# TOP.net
KiCad netlist of a schematic drawn in Altium Designer
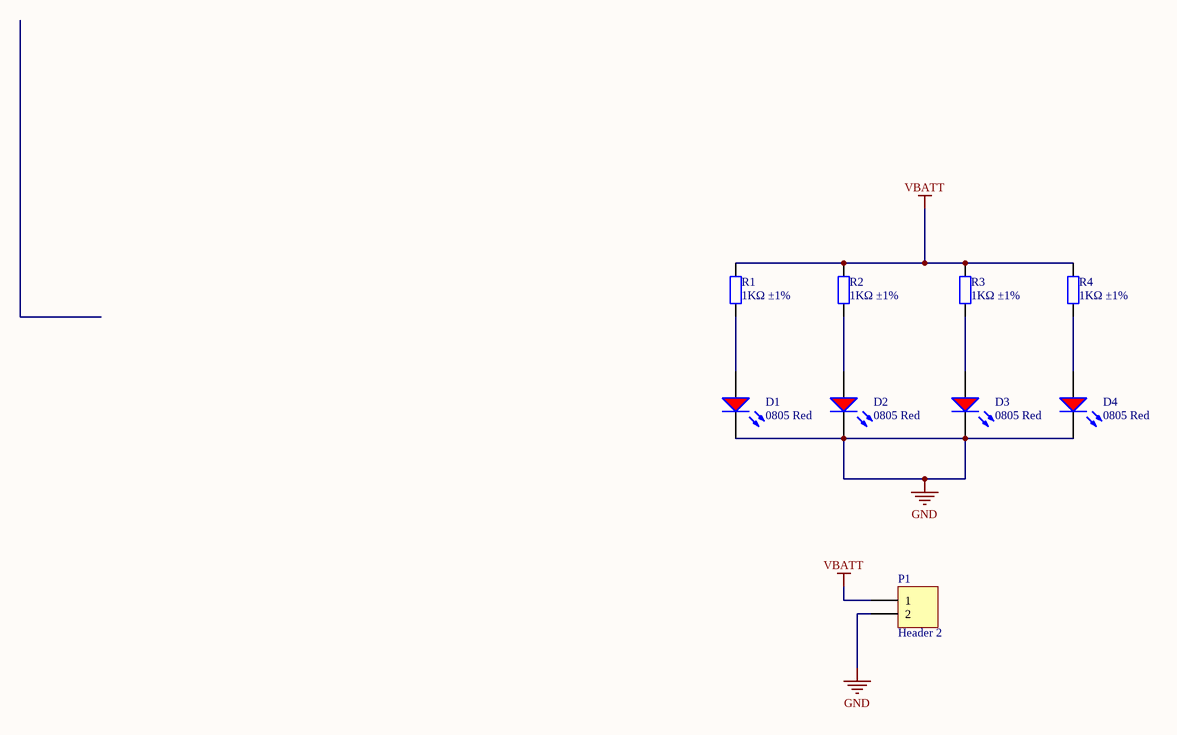
[diagram p0: TOP.SchDoc]

(export (version "E")
  (design (tool "Eeschema 10.0.6"))
  (components
    (comp (ref "D1")
      (value "0805 Red")
      (footprint "0805_LED_S1")
      (description "LED")
      (libsource (lib "Miscellaneous Devices LC") (part "0805 LED Red"))
    )
    (comp (ref "D2")
      (value "0805 Red")
      (footprint "0805_LED_S1")
      (description "LED")
      (libsource (lib "Miscellaneous Devices LC") (part "0805 LED Red"))
    )
    (comp (ref "D3")
      (value "0805 Red")
      (footprint "0805_LED_S1")
      (description "LED")
      (libsource (lib "Miscellaneous Devices LC") (part "0805 LED Red"))
    )
    (comp (ref "D4")
      (value "0805 Red")
      (footprint "0805_LED_S1")
      (description "LED")
      (libsource (lib "Miscellaneous Devices LC") (part "0805 LED Red"))
    )
    (comp (ref "P1")
      (value "Header 2")
      (footprint "HDR1X2")
      (description "Header, 2-Pin")
      (fields (field (name "PUBLISHER") "Altium Limited"))
      (libsource (lib "Miscellaneous Connectors") (part "Header 2"))
    )
    (comp (ref "R1")
      (value "1KΩ ±1%")
      (footprint "0402_R")
      (description "Chip resistor")
      (fields (field (name "MANUFACTURER") "Uniroyal Elec") (field (name "PARTNUMBER") "0402WGF1001TCE"))
      (libsource (lib "Miscellaneous Devices LC") (part "0402 1K (1001) 1%"))
    )
    (comp (ref "R2")
      (value "1KΩ ±1%")
      (footprint "0402_R")
      (description "Chip resistor")
      (fields (field (name "MANUFACTURER") "Uniroyal Elec") (field (name "PARTNUMBER") "0402WGF1001TCE"))
      (libsource (lib "Miscellaneous Devices LC") (part "0402 1K (1001) 1%"))
    )
    (comp (ref "R3")
      (value "1KΩ ±1%")
      (footprint "0402_R")
      (description "Chip resistor")
      (fields (field (name "MANUFACTURER") "Uniroyal Elec") (field (name "PARTNUMBER") "0402WGF1001TCE"))
      (libsource (lib "Miscellaneous Devices LC") (part "0402 1K (1001) 1%"))
    )
    (comp (ref "R4")
      (value "1KΩ ±1%")
      (footprint "0402_R")
      (description "Chip resistor")
      (fields (field (name "MANUFACTURER") "Uniroyal Elec") (field (name "PARTNUMBER") "0402WGF1001TCE"))
      (libsource (lib "Miscellaneous Devices LC") (part "0402 1K (1001) 1%"))
    )
  )
  (nets
    (net (code "1") (name "GND") (class "Default")
      (node (ref "D1") (pin "K") (pinfunction "K_K") (pintype "passive"))
      (node (ref "D2") (pin "K") (pinfunction "K_K") (pintype "passive"))
      (node (ref "D3") (pin "K") (pinfunction "K_K") (pintype "passive"))
      (node (ref "D4") (pin "K") (pinfunction "K_K") (pintype "passive"))
      (node (ref "P1") (pin "2") (pinfunction "2_2") (pintype "passive"))
    )
    (net (code "2") (name "Net-(D1-PadA)") (class "Default")
      (node (ref "D1") (pin "A") (pinfunction "A_A") (pintype "passive"))
      (node (ref "R1") (pin "1") (pinfunction "1_1") (pintype "passive"))
    )
    (net (code "3") (name "Net-(D2-PadA)") (class "Default")
      (node (ref "D2") (pin "A") (pinfunction "A_A") (pintype "passive"))
      (node (ref "R2") (pin "1") (pinfunction "1_1") (pintype "passive"))
    )
    (net (code "4") (name "Net-(D3-PadA)") (class "Default")
      (node (ref "D3") (pin "A") (pinfunction "A_A") (pintype "passive"))
      (node (ref "R3") (pin "1") (pinfunction "1_1") (pintype "passive"))
    )
    (net (code "5") (name "Net-(D4-PadA)") (class "Default")
      (node (ref "D4") (pin "A") (pinfunction "A_A") (pintype "passive"))
      (node (ref "R4") (pin "1") (pinfunction "1_1") (pintype "passive"))
    )
    (net (code "6") (name "VBATT") (class "Default")
      (node (ref "P1") (pin "1") (pinfunction "1_1") (pintype "passive"))
      (node (ref "R1") (pin "2") (pinfunction "2_2") (pintype "passive"))
      (node (ref "R2") (pin "2") (pinfunction "2_2") (pintype "passive"))
      (node (ref "R3") (pin "2") (pinfunction "2_2") (pintype "passive"))
      (node (ref "R4") (pin "2") (pinfunction "2_2") (pintype "passive"))
    )
  )
)
